# SATA.net
KiCad netlist of a schematic drawn in Altium Designer
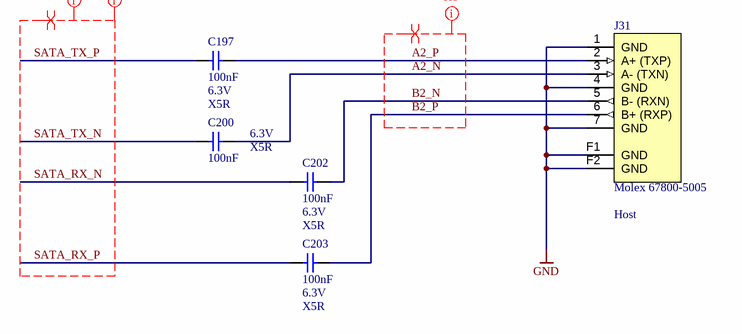
[diagram p0: SATA.schdoc]

(export (version "E")
  (design (tool "Eeschema 10.0.6"))
  (components
    (comp (ref "C197")
      (value "100nF")
      (footprint "CAPC0603X33N")
      (description "KON 100nF 6.3V X5R SMD 10%")
      (fields
        (field (name "VOLTAGE") "6.3V")
        (field (name "TECHNOLOGY") "X5R")
        (field (name "TOLERANCE") "10%")
      )
      (libsource (lib "TE") (part "CAP-NP"))
    )
    (comp (ref "C200")
      (value "100nF")
      (footprint "CAPC0603X33N")
      (description "KON 100nF 6.3V X5R SMD 10%")
      (fields
        (field (name "VOLTAGE") "6.3V")
        (field (name "TECHNOLOGY") "X5R")
        (field (name "TOLERANCE") "10%")
      )
      (libsource (lib "TE") (part "CAP-NP"))
    )
    (comp (ref "C202")
      (value "100nF")
      (footprint "CAPC0603X33N")
      (description "KON 100nF 6.3V X5R SMD 10%")
      (fields
        (field (name "VOLTAGE") "6.3V")
        (field (name "TECHNOLOGY") "X5R")
        (field (name "TOLERANCE") "10%")
      )
      (libsource (lib "TE") (part "CAP-NP"))
    )
    (comp (ref "C203")
      (value "100nF")
      (footprint "CAPC0603X33N")
      (description "KON 100nF 6.3V X5R SMD 10%")
      (fields
        (field (name "VOLTAGE") "6.3V")
        (field (name "TECHNOLOGY") "X5R")
        (field (name "TOLERANCE") "10%")
      )
      (libsource (lib "TE") (part "CAP-NP"))
    )
    (comp (ref "J31")
      (value "Molex 67800-5005")
      (footprint "67800-5005")
      (description "SATA 7Pol. Connector Vertical")
      (libsource (lib "TE") (part "SATA"))
    )
  )
  (nets
    (net (code "1") (name "/A2_N") (class "Default")
      (node (ref "C200") (pin "2") (pinfunction "2_2") (pintype "passive"))
      (node (ref "J31") (pin "3") (pinfunction "A-_(TXN)_3") (pintype "input"))
    )
    (net (code "2") (name "/A2_P") (class "Default")
      (node (ref "C197") (pin "2") (pinfunction "2_2") (pintype "passive"))
      (node (ref "J31") (pin "2") (pinfunction "A+_(TXP)_2") (pintype "input"))
    )
    (net (code "3") (name "/B2_N") (class "Default")
      (node (ref "C202") (pin "2") (pinfunction "2_2") (pintype "passive"))
      (node (ref "J31") (pin "5") (pinfunction "B-_(RXN)_5") (pintype "output"))
    )
    (net (code "4") (name "/B2_P") (class "Default")
      (node (ref "C203") (pin "2") (pinfunction "2_2") (pintype "passive"))
      (node (ref "J31") (pin "6") (pinfunction "B+_(RXP)_6") (pintype "output"))
    )
    (net (code "5") (name "/SATA_RX_N") (class "Default")
      (node (ref "C202") (pin "1") (pinfunction "1_1") (pintype "passive"))
    )
    (net (code "6") (name "/SATA_RX_P") (class "Default")
      (node (ref "C203") (pin "1") (pinfunction "1_1") (pintype "passive"))
    )
    (net (code "7") (name "/SATA_TX_N") (class "Default")
      (node (ref "C200") (pin "1") (pinfunction "1_1") (pintype "passive"))
    )
    (net (code "8") (name "/SATA_TX_P") (class "Default")
      (node (ref "C197") (pin "1") (pinfunction "1_1") (pintype "passive"))
    )
    (net (code "9") (name "GND") (class "Default")
      (node (ref "J31") (pin "1") (pinfunction "GND_1") (pintype "power_in"))
      (node (ref "J31") (pin "4") (pinfunction "GND_4") (pintype "power_in"))
      (node (ref "J31") (pin "7") (pinfunction "GND_7") (pintype "power_in"))
      (node (ref "J31") (pin "F1") (pinfunction "GND_F1") (pintype "power_in"))
      (node (ref "J31") (pin "F2") (pinfunction "GND_F2") (pintype "power_in"))
    )
  )
)
